# NIR_Schematic.net
KiCad netlist of a schematic drawn in EasyEDA
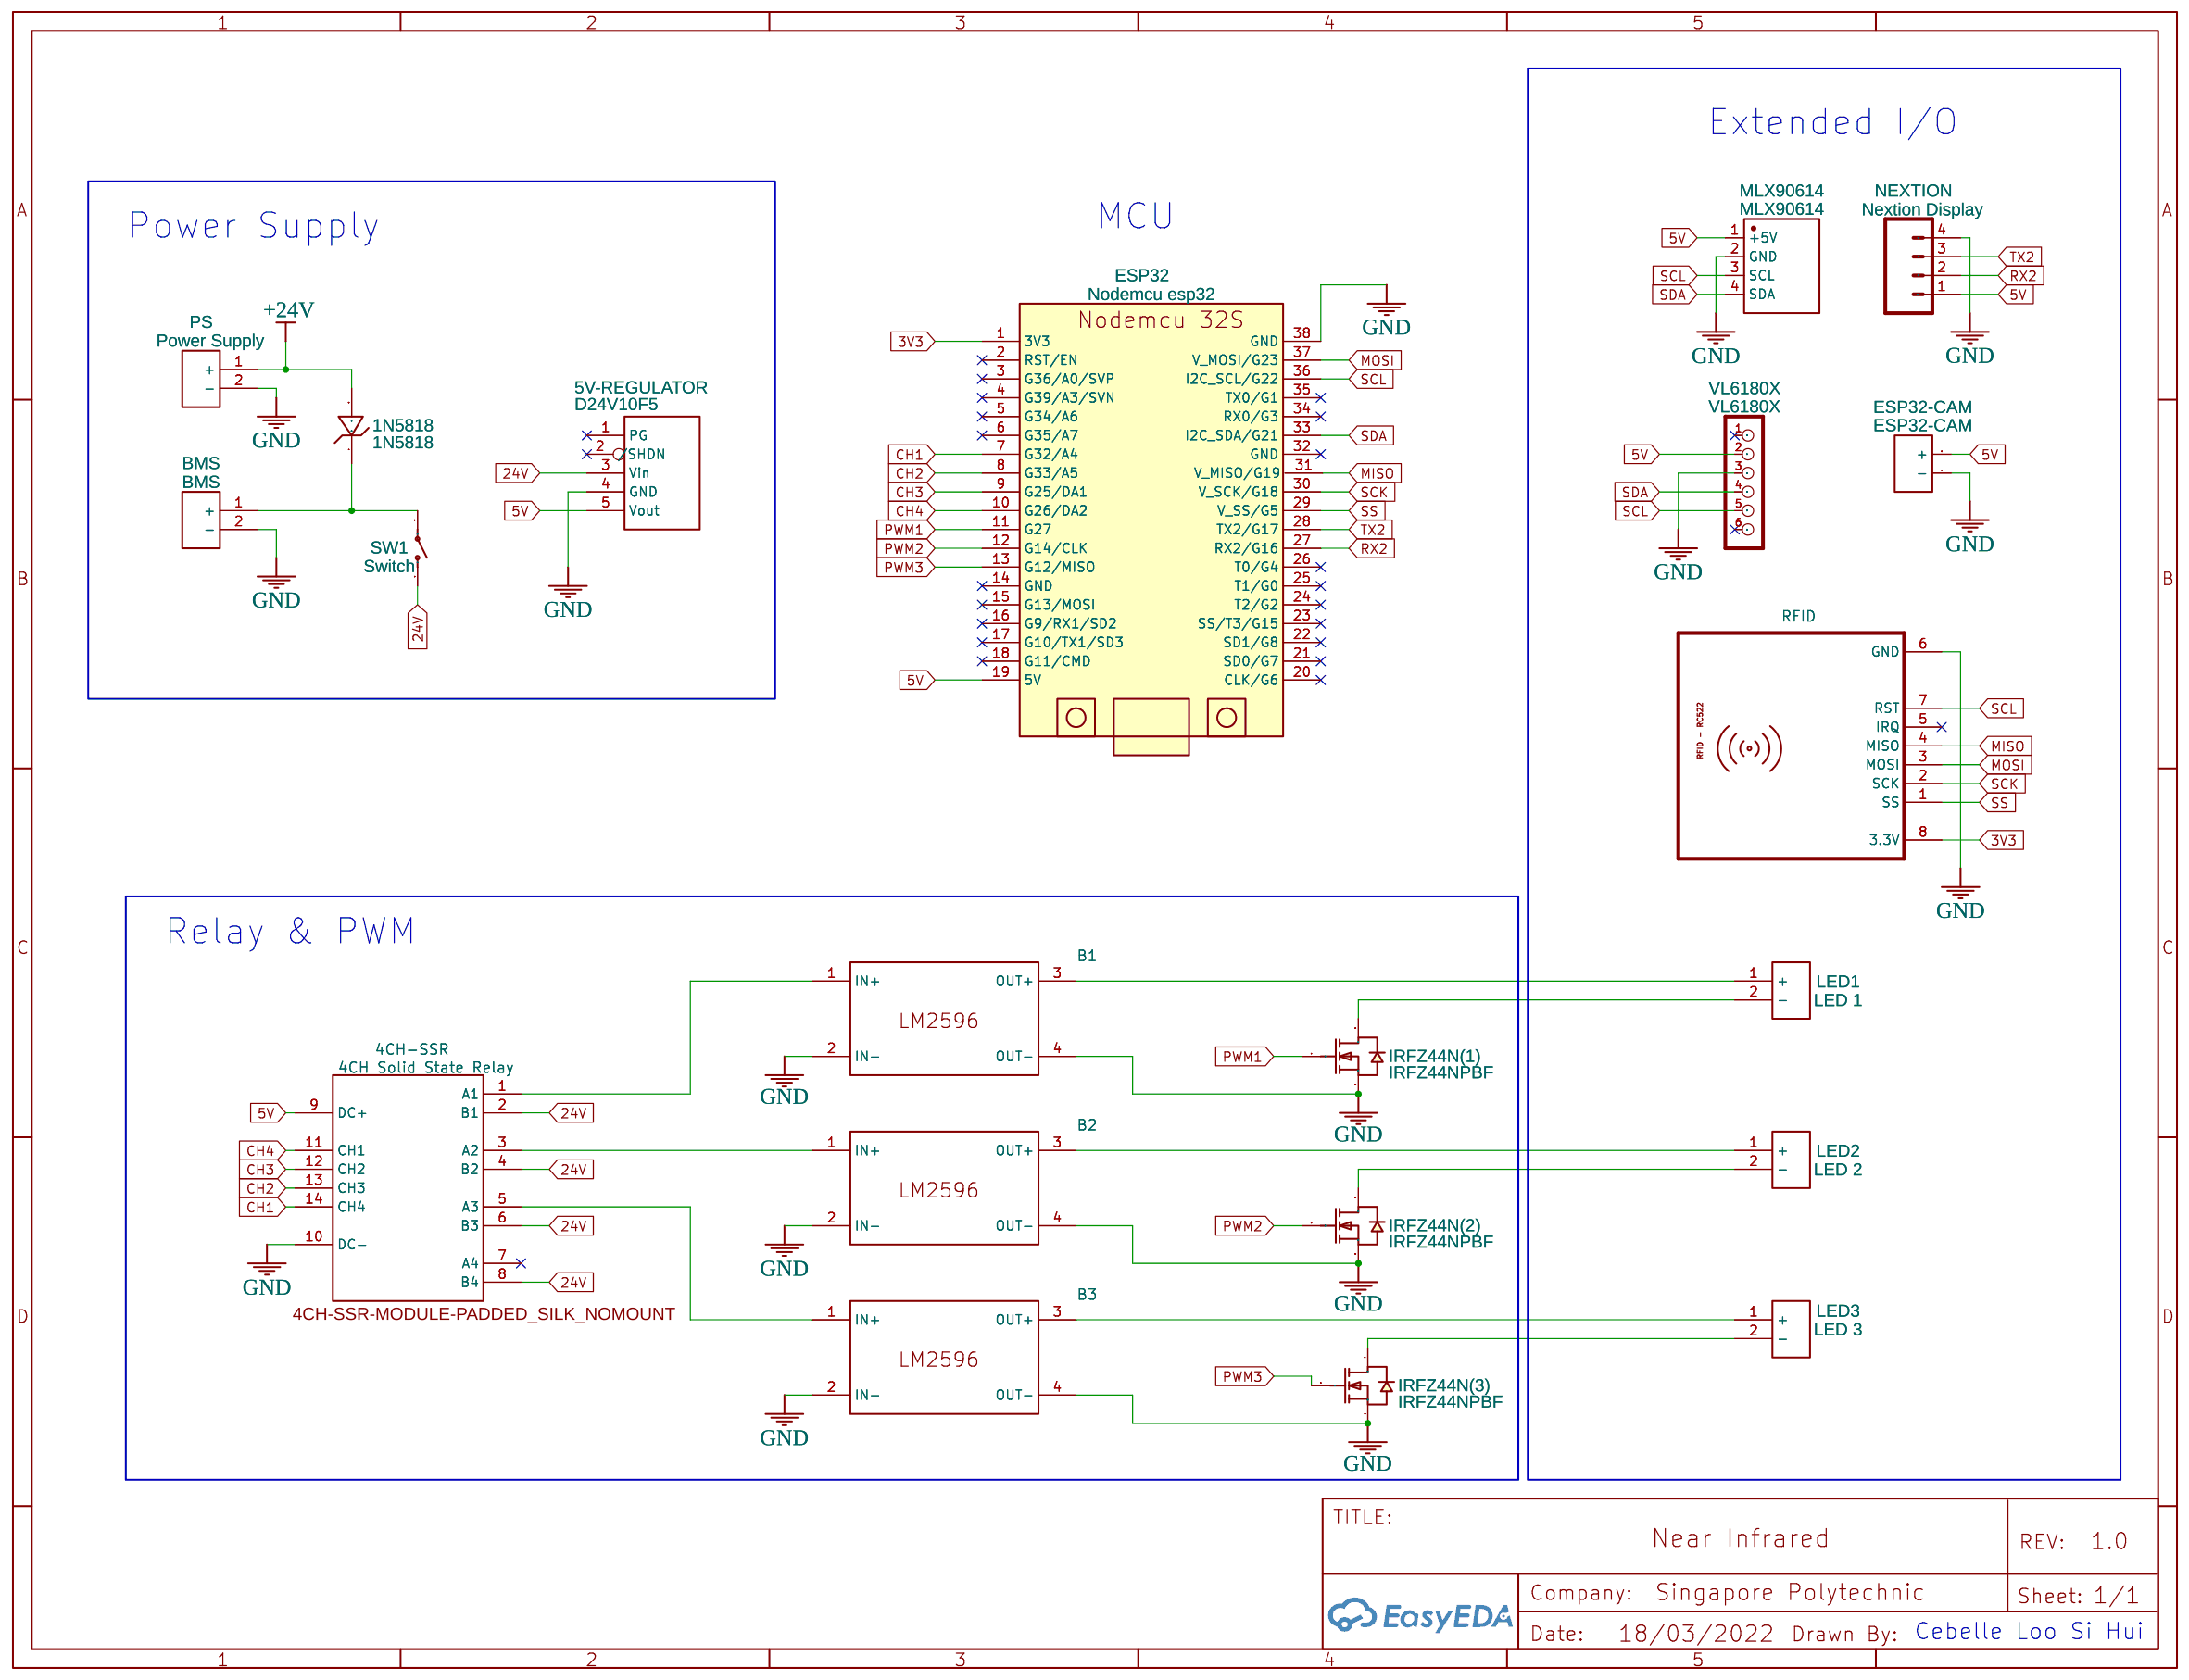
[diagram p0: schematic sheet]

(export (version "E")
  (design (tool "Eeschema 10.0.6"))
  (components
    (comp (ref "1N5818")
      (value "1N5818")
      (fields (field (name "BOM_Supplier Part") "C402217"))
      (libsource (lib "") (part "1N5818"))
    )
    (comp (ref "4CH-SSR") (value "4CH Solid State Relay") (libsource (lib "") (part "Unknown_210_-255")))
    (comp (ref "5V-REGULATOR") (value "D24V10F5") (libsource (lib "") (part "D24V10F5")))
    (comp (ref "B1") (value "NO") (libsource (lib "") (part "Unknown_495_-345")))
    (comp (ref "B2") (value "NO") (libsource (lib "") (part "Unknown_495_-255")))
    (comp (ref "B3") (value "NO") (libsource (lib "") (part "Unknown_495_-165")))
    (comp (ref "BMS")
      (value "BMS")
      (fields
        (field (name "BOM_Manufacturer Part") "WJ103-5.00-2P")
        (field (name "BOM_Supplier Part") "C8439")
      )
      (libsource (lib "") (part "WJ103-5.00-2P_1"))
    )
    (comp (ref "ESP32") (value "Nodemcu esp32") (libsource (lib "") (part "Nodemcu esp32")))
    (comp (ref "ESP32-CAM")
      (value "ESP32-CAM")
      (fields
        (field (name "BOM_Manufacturer Part") "2.54-1*2PFemale")
        (field (name "BOM_Supplier Part") "C49661")
      )
      (libsource (lib "") (part "Header-Female-2.54_1x2"))
    )
    (comp (ref "IRFZ44N(1)")
      (value "IRFZ44NPBF")
      (fields (field (name "BOM_Supplier Part") "C2586"))
      (libsource (lib "") (part "IRFZ44NPBF_1"))
    )
    (comp (ref "IRFZ44N(2)")
      (value "IRFZ44NPBF")
      (fields (field (name "BOM_Supplier Part") "C2586"))
      (libsource (lib "") (part "IRFZ44NPBF_2"))
    )
    (comp (ref "IRFZ44N(3)")
      (value "IRFZ44NPBF")
      (fields (field (name "BOM_Supplier Part") "C2586"))
      (libsource (lib "") (part "IRFZ44NPBF"))
    )
    (comp (ref "LED1")
      (value "LED 1")
      (fields
        (field (name "BOM_Manufacturer Part") "WJ103-5.00-2P")
        (field (name "BOM_Supplier Part") "C8439")
      )
      (libsource (lib "") (part "WJ103-5.00-2P"))
    )
    (comp (ref "LED2")
      (value "LED 2")
      (fields
        (field (name "BOM_Manufacturer Part") "WJ103-5.00-2P")
        (field (name "BOM_Supplier Part") "C8439")
      )
      (libsource (lib "") (part "WJ103-5.00-2P"))
    )
    (comp (ref "LED3")
      (value "LED 3")
      (fields
        (field (name "BOM_Manufacturer Part") "WJ103-5.00-2P")
        (field (name "BOM_Supplier Part") "C8439")
      )
      (libsource (lib "") (part "WJ103-5.00-2P"))
    )
    (comp (ref "MLX90614")
      (value "MLX90614")
      (fields
        (field (name "BOM_Manufacturer Part") "RE-H042TD-1190(LF)(SN)")
        (field (name "BOM_Supplier Part") "C265319")
      )
      (libsource (lib "") (part "RE-H042TD-1190(LF)(SN)"))
    )
    (comp (ref "NEXTION") (value "Nextion Display") (libsource (lib "") (part "M04POLAR")))
    (comp (ref "PS")
      (value "Power Supply")
      (fields
        (field (name "BOM_Manufacturer Part") "WJ103-5.00-2P")
        (field (name "BOM_Supplier Part") "C8439")
      )
      (libsource (lib "") (part "WJ103-5.00-2P_2"))
    )
    (comp (ref "RFID") (value "NO") (libsource (lib "") (part "Unknown_954_-490")))
    (comp (ref "SW1")
      (value "Switch")
      (fields (field (name "BOM_Manufacturer Part") "KCD1-11-1.5x1cm"))
      (libsource (lib "") (part "SWITCH-2P-SPST-Rocker-10x15mm"))
    )
    (comp (ref "VL6180X") (value "VL6180X") (libsource (lib "") (part "CON_HEADER_1X06-PTH")))
  )
  (nets
    (net (code "1") (name "+24V") (class "Default")
      (node (ref "1N5818") (pin "2") (pinfunction "A_2") (pintype "unspecified"))
      (node (ref "PS") (pin "1") (pinfunction "+_1") (pintype "unspecified"))
    )
    (net (code "2") (name "3V3") (class "Default")
      (node (ref "ESP32") (pin "1") (pinfunction "3V3_1") (pintype "passive"))
      (node (ref "RFID") (pin "8") (pinfunction "3.3V_8") (pintype "unspecified"))
    )
    (net (code "3") (name "5V") (class "Default")
      (node (ref "4CH-SSR") (pin "9") (pinfunction "DC+_9") (pintype "unspecified"))
      (node (ref "5V-REGULATOR") (pin "5") (pinfunction "Vout_5") (pintype "unspecified"))
      (node (ref "ESP32") (pin "19") (pinfunction "5V_19") (pintype "passive"))
      (node (ref "ESP32-CAM") (pin "2") (pinfunction "+_2") (pintype "input"))
      (node (ref "MLX90614") (pin "1") (pinfunction "+5V_1") (pintype "unspecified"))
      (node (ref "NEXTION") (pin "1") (pinfunction "GND_1") (pintype "unspecified"))
      (node (ref "VL6180X") (pin "2") (pinfunction "VIN_2") (pintype "unspecified"))
    )
    (net (code "4") (name "24V") (class "Default")
      (node (ref "4CH-SSR") (pin "2") (pinfunction "B1_2") (pintype "unspecified"))
      (node (ref "4CH-SSR") (pin "4") (pinfunction "B2_4") (pintype "unspecified"))
      (node (ref "4CH-SSR") (pin "6") (pinfunction "B3_6") (pintype "unspecified"))
      (node (ref "4CH-SSR") (pin "8") (pinfunction "B4_8") (pintype "unspecified"))
      (node (ref "5V-REGULATOR") (pin "3") (pinfunction "Vin_3") (pintype "unspecified"))
      (node (ref "SW1") (pin "1") (pinfunction "O_1") (pintype "unspecified"))
    )
    (net (code "5") (name "CH1") (class "Default")
      (node (ref "4CH-SSR") (pin "14") (pinfunction "CH4_14") (pintype "unspecified"))
      (node (ref "ESP32") (pin "7") (pinfunction "G32/A4_7") (pintype "bidirectional"))
    )
    (net (code "6") (name "CH2") (class "Default")
      (node (ref "4CH-SSR") (pin "13") (pinfunction "CH3_13") (pintype "unspecified"))
      (node (ref "ESP32") (pin "8") (pinfunction "G33/A5_8") (pintype "bidirectional"))
    )
    (net (code "7") (name "CH3") (class "Default")
      (node (ref "4CH-SSR") (pin "12") (pinfunction "CH2_12") (pintype "unspecified"))
      (node (ref "ESP32") (pin "9") (pinfunction "G25/DA1_9") (pintype "bidirectional"))
    )
    (net (code "8") (name "CH4") (class "Default")
      (node (ref "4CH-SSR") (pin "11") (pinfunction "CH1_11") (pintype "unspecified"))
      (node (ref "ESP32") (pin "10") (pinfunction "G26/DA2_10") (pintype "bidirectional"))
    )
    (net (code "9") (name "GND") (class "Default")
      (node (ref "4CH-SSR") (pin "10") (pinfunction "DC-_10") (pintype "unspecified"))
      (node (ref "5V-REGULATOR") (pin "4") (pinfunction "GND_4") (pintype "unspecified"))
      (node (ref "B1") (pin "2") (pinfunction "IN-_2") (pintype "unspecified"))
      (node (ref "B1") (pin "4") (pinfunction "OUT-_4") (pintype "unspecified"))
      (node (ref "B2") (pin "2") (pinfunction "IN-_2") (pintype "unspecified"))
      (node (ref "B2") (pin "4") (pinfunction "OUT-_4") (pintype "unspecified"))
      (node (ref "B3") (pin "2") (pinfunction "IN-_2") (pintype "unspecified"))
      (node (ref "B3") (pin "4") (pinfunction "OUT-_4") (pintype "unspecified"))
      (node (ref "BMS") (pin "2") (pinfunction "-_2") (pintype "unspecified"))
      (node (ref "ESP32") (pin "38") (pinfunction "GND_38") (pintype "passive"))
      (node (ref "ESP32-CAM") (pin "1") (pinfunction "-_1") (pintype "input"))
      (node (ref "IRFZ44N(1)") (pin "3") (pinfunction "S_3") (pintype "unspecified"))
      (node (ref "IRFZ44N(2)") (pin "3") (pinfunction "S_3") (pintype "unspecified"))
      (node (ref "IRFZ44N(3)") (pin "3") (pinfunction "S_3") (pintype "unspecified"))
      (node (ref "MLX90614") (pin "2") (pinfunction "GND_2") (pintype "unspecified"))
      (node (ref "NEXTION") (pin "4") (pinfunction "+5V_4") (pintype "unspecified"))
      (node (ref "PS") (pin "2") (pinfunction "-_2") (pintype "unspecified"))
      (node (ref "RFID") (pin "6") (pinfunction "GND_6") (pintype "unspecified"))
      (node (ref "VL6180X") (pin "3") (pinfunction "GND_3") (pintype "unspecified"))
    )
    (net (code "10") (name "MISO") (class "Default")
      (node (ref "ESP32") (pin "31") (pinfunction "V_MISO/G19_31") (pintype "bidirectional"))
      (node (ref "RFID") (pin "4") (pinfunction "MISO_4") (pintype "unspecified"))
    )
    (net (code "11") (name "MOSI") (class "Default")
      (node (ref "ESP32") (pin "37") (pinfunction "V_MOSI/G23_37") (pintype "bidirectional"))
      (node (ref "RFID") (pin "3") (pinfunction "MOSI_3") (pintype "unspecified"))
    )
    (net (code "12") (name "Net-(1N5818-C)") (class "Default")
      (node (ref "1N5818") (pin "1") (pinfunction "C_1") (pintype "unspecified"))
      (node (ref "BMS") (pin "1") (pinfunction "+_1") (pintype "unspecified"))
      (node (ref "SW1") (pin "2") (pinfunction "P_2") (pintype "unspecified"))
    )
    (net (code "13") (name "Net-(4CH-SSR-A1)") (class "Default")
      (node (ref "4CH-SSR") (pin "1") (pinfunction "A1_1") (pintype "unspecified"))
      (node (ref "B1") (pin "1") (pinfunction "IN+_1") (pintype "unspecified"))
    )
    (net (code "14") (name "Net-(4CH-SSR-A2)") (class "Default")
      (node (ref "4CH-SSR") (pin "3") (pinfunction "A2_3") (pintype "unspecified"))
      (node (ref "B2") (pin "1") (pinfunction "IN+_1") (pintype "unspecified"))
    )
    (net (code "15") (name "Net-(4CH-SSR-A3)") (class "Default")
      (node (ref "4CH-SSR") (pin "5") (pinfunction "A3_5") (pintype "unspecified"))
      (node (ref "B3") (pin "1") (pinfunction "IN+_1") (pintype "unspecified"))
    )
    (net (code "16") (name "Net-(B1-OUT+)") (class "Default")
      (node (ref "B1") (pin "3") (pinfunction "OUT+_3") (pintype "unspecified"))
      (node (ref "LED1") (pin "1") (pinfunction "+_1") (pintype "unspecified"))
    )
    (net (code "17") (name "Net-(B2-OUT+)") (class "Default")
      (node (ref "B2") (pin "3") (pinfunction "OUT+_3") (pintype "unspecified"))
      (node (ref "LED2") (pin "1") (pinfunction "+_1") (pintype "unspecified"))
    )
    (net (code "18") (name "Net-(B3-OUT+)") (class "Default")
      (node (ref "B3") (pin "3") (pinfunction "OUT+_3") (pintype "unspecified"))
      (node (ref "LED3") (pin "1") (pinfunction "+_1") (pintype "unspecified"))
    )
    (net (code "19") (name "Net-(IRFZ44N(1)-D)") (class "Default")
      (node (ref "IRFZ44N(1)") (pin "2") (pinfunction "D_2") (pintype "unspecified"))
      (node (ref "LED1") (pin "2") (pinfunction "-_2") (pintype "unspecified"))
    )
    (net (code "20") (name "Net-(IRFZ44N(2)-D)") (class "Default")
      (node (ref "IRFZ44N(2)") (pin "2") (pinfunction "D_2") (pintype "unspecified"))
      (node (ref "LED2") (pin "2") (pinfunction "-_2") (pintype "unspecified"))
    )
    (net (code "21") (name "Net-(IRFZ44N(3)-D)") (class "Default")
      (node (ref "IRFZ44N(3)") (pin "2") (pinfunction "D_2") (pintype "unspecified"))
      (node (ref "LED3") (pin "2") (pinfunction "-_2") (pintype "unspecified"))
    )
    (net (code "22") (name "PWM1") (class "Default")
      (node (ref "ESP32") (pin "11") (pinfunction "G27_11") (pintype "bidirectional"))
      (node (ref "IRFZ44N(1)") (pin "1") (pinfunction "G_1") (pintype "unspecified"))
    )
    (net (code "23") (name "PWM2") (class "Default")
      (node (ref "ESP32") (pin "12") (pinfunction "G14/CLK_12") (pintype "bidirectional"))
      (node (ref "IRFZ44N(2)") (pin "1") (pinfunction "G_1") (pintype "unspecified"))
    )
    (net (code "24") (name "PWM3") (class "Default")
      (node (ref "ESP32") (pin "13") (pinfunction "G12/MISO_13") (pintype "bidirectional"))
      (node (ref "IRFZ44N(3)") (pin "1") (pinfunction "G_1") (pintype "unspecified"))
    )
    (net (code "25") (name "RX2") (class "Default")
      (node (ref "ESP32") (pin "27") (pinfunction "RX2/G16_27") (pintype "bidirectional"))
      (node (ref "NEXTION") (pin "2") (pinfunction "RX_2") (pintype "unspecified"))
    )
    (net (code "26") (name "SCK") (class "Default")
      (node (ref "ESP32") (pin "30") (pinfunction "V_SCK/G18_30") (pintype "bidirectional"))
      (node (ref "RFID") (pin "2") (pinfunction "SCK_2") (pintype "unspecified"))
    )
    (net (code "27") (name "SCL") (class "Default")
      (node (ref "ESP32") (pin "36") (pinfunction "I2C_SCL/G22_36") (pintype "bidirectional"))
      (node (ref "MLX90614") (pin "3") (pinfunction "SCL_3") (pintype "unspecified"))
      (node (ref "RFID") (pin "7") (pinfunction "RST_7") (pintype "unspecified"))
      (node (ref "VL6180X") (pin "5") (pinfunction "SCL_5") (pintype "unspecified"))
    )
    (net (code "28") (name "SDA") (class "Default")
      (node (ref "ESP32") (pin "33") (pinfunction "I2C_SDA/G21_33") (pintype "bidirectional"))
      (node (ref "MLX90614") (pin "4") (pinfunction "SDA_4") (pintype "unspecified"))
      (node (ref "VL6180X") (pin "4") (pinfunction "SDA_4") (pintype "unspecified"))
    )
    (net (code "29") (name "SS") (class "Default")
      (node (ref "ESP32") (pin "29") (pinfunction "V_SS/G5_29") (pintype "bidirectional"))
      (node (ref "RFID") (pin "1") (pinfunction "SS_1") (pintype "unspecified"))
    )
    (net (code "30") (name "TX2") (class "Default")
      (node (ref "ESP32") (pin "28") (pinfunction "TX2/G17_28") (pintype "bidirectional"))
      (node (ref "NEXTION") (pin "3") (pinfunction "TX_3") (pintype "unspecified"))
    )
    (net (code "31") (name "unconnected-(4CH-SSR-A4-Pad7)") (class "Default")
      (node (ref "4CH-SSR") (pin "7") (pinfunction "A4_7") (pintype "unspecified+no_connect"))
    )
    (net (code "32") (name "unconnected-(5V-REGULATOR-PG-Pad1)") (class "Default")
      (node (ref "5V-REGULATOR") (pin "1") (pinfunction "PG_1") (pintype "unspecified+no_connect"))
    )
    (net (code "33") (name "unconnected-(5V-REGULATOR-{slash}SHDN-Pad2)") (class "Default")
      (node (ref "5V-REGULATOR") (pin "2") (pinfunction "/SHDN_2") (pintype "unspecified+no_connect"))
    )
    (net (code "34") (name "unconnected-(ESP32-CLK{slash}G6-Pad20)") (class "Default")
      (node (ref "ESP32") (pin "20") (pinfunction "CLK/G6_20") (pintype "bidirectional+no_connect"))
    )
    (net (code "35") (name "unconnected-(ESP32-G9{slash}RX1{slash}SD2-Pad16)") (class "Default")
      (node (ref "ESP32") (pin "16") (pinfunction "G9/RX1/SD2_16") (pintype "bidirectional+no_connect"))
    )
    (net (code "36") (name "unconnected-(ESP32-G10{slash}TX1{slash}SD3-Pad17)") (class "Default")
      (node (ref "ESP32") (pin "17") (pinfunction "G10/TX1/SD3_17") (pintype "bidirectional+no_connect"))
    )
    (net (code "37") (name "unconnected-(ESP32-G11{slash}CMD-Pad18)") (class "Default")
      (node (ref "ESP32") (pin "18") (pinfunction "G11/CMD_18") (pintype "bidirectional+no_connect"))
    )
    (net (code "38") (name "unconnected-(ESP32-G13{slash}MOSI-Pad15)") (class "Default")
      (node (ref "ESP32") (pin "15") (pinfunction "G13/MOSI_15") (pintype "bidirectional+no_connect"))
    )
    (net (code "39") (name "unconnected-(ESP32-G34{slash}A6-Pad5)") (class "Default")
      (node (ref "ESP32") (pin "5") (pinfunction "G34/A6_5") (pintype "bidirectional+no_connect"))
    )
    (net (code "40") (name "unconnected-(ESP32-G35{slash}A7-Pad6)") (class "Default")
      (node (ref "ESP32") (pin "6") (pinfunction "G35/A7_6") (pintype "bidirectional+no_connect"))
    )
    (net (code "41") (name "unconnected-(ESP32-G36{slash}A0{slash}SVP-Pad3)") (class "Default")
      (node (ref "ESP32") (pin "3") (pinfunction "G36/A0/SVP_3") (pintype "bidirectional+no_connect"))
    )
    (net (code "42") (name "unconnected-(ESP32-G39{slash}A3{slash}SVN-Pad4)") (class "Default")
      (node (ref "ESP32") (pin "4") (pinfunction "G39/A3/SVN_4") (pintype "bidirectional+no_connect"))
    )
    (net (code "43") (name "unconnected-(ESP32-GND-Pad14)") (class "Default")
      (node (ref "ESP32") (pin "14") (pinfunction "GND_14") (pintype "passive+no_connect"))
    )
    (net (code "44") (name "unconnected-(ESP32-GND-Pad32)") (class "Default")
      (node (ref "ESP32") (pin "32") (pinfunction "GND_32") (pintype "passive+no_connect"))
    )
    (net (code "45") (name "unconnected-(ESP32-RST{slash}EN-Pad2)") (class "Default")
      (node (ref "ESP32") (pin "2") (pinfunction "RST/EN_2") (pintype "bidirectional+no_connect"))
    )
    (net (code "46") (name "unconnected-(ESP32-RX0{slash}G3-Pad34)") (class "Default")
      (node (ref "ESP32") (pin "34") (pinfunction "RX0/G3_34") (pintype "bidirectional+no_connect"))
    )
    (net (code "47") (name "unconnected-(ESP32-SD0{slash}G7-Pad21)") (class "Default")
      (node (ref "ESP32") (pin "21") (pinfunction "SD0/G7_21") (pintype "bidirectional+no_connect"))
    )
    (net (code "48") (name "unconnected-(ESP32-SD1{slash}G8-Pad22)") (class "Default")
      (node (ref "ESP32") (pin "22") (pinfunction "SD1/G8_22") (pintype "bidirectional+no_connect"))
    )
    (net (code "49") (name "unconnected-(ESP32-SS{slash}T3{slash}G15-Pad23)") (class "Default")
      (node (ref "ESP32") (pin "23") (pinfunction "SS/T3/G15_23") (pintype "bidirectional+no_connect"))
    )
    (net (code "50") (name "unconnected-(ESP32-T0{slash}G4-Pad26)") (class "Default")
      (node (ref "ESP32") (pin "26") (pinfunction "T0/G4_26") (pintype "bidirectional+no_connect"))
    )
    (net (code "51") (name "unconnected-(ESP32-T1{slash}G0-Pad25)") (class "Default")
      (node (ref "ESP32") (pin "25") (pinfunction "T1/G0_25") (pintype "bidirectional+no_connect"))
    )
    (net (code "52") (name "unconnected-(ESP32-T2{slash}G2-Pad24)") (class "Default")
      (node (ref "ESP32") (pin "24") (pinfunction "T2/G2_24") (pintype "bidirectional+no_connect"))
    )
    (net (code "53") (name "unconnected-(ESP32-TX0{slash}G1-Pad35)") (class "Default")
      (node (ref "ESP32") (pin "35") (pinfunction "TX0/G1_35") (pintype "bidirectional+no_connect"))
    )
    (net (code "54") (name "unconnected-(RFID-IRQ-Pad5)") (class "Default")
      (node (ref "RFID") (pin "5") (pinfunction "IRQ_5") (pintype "unspecified+no_connect"))
    )
    (net (code "55") (name "unconnected-(VL6180X-IO1-Pad6)") (class "Default")
      (node (ref "VL6180X") (pin "6") (pinfunction "IO1_6") (pintype "unspecified+no_connect"))
    )
    (net (code "56") (name "unconnected-(VL6180X-VDD-Pad1)") (class "Default")
      (node (ref "VL6180X") (pin "1") (pinfunction "VDD_1") (pintype "unspecified+no_connect"))
    )
  )
)
